# SWITCHING.net
KiCad netlist of a schematic drawn in Altium Designer
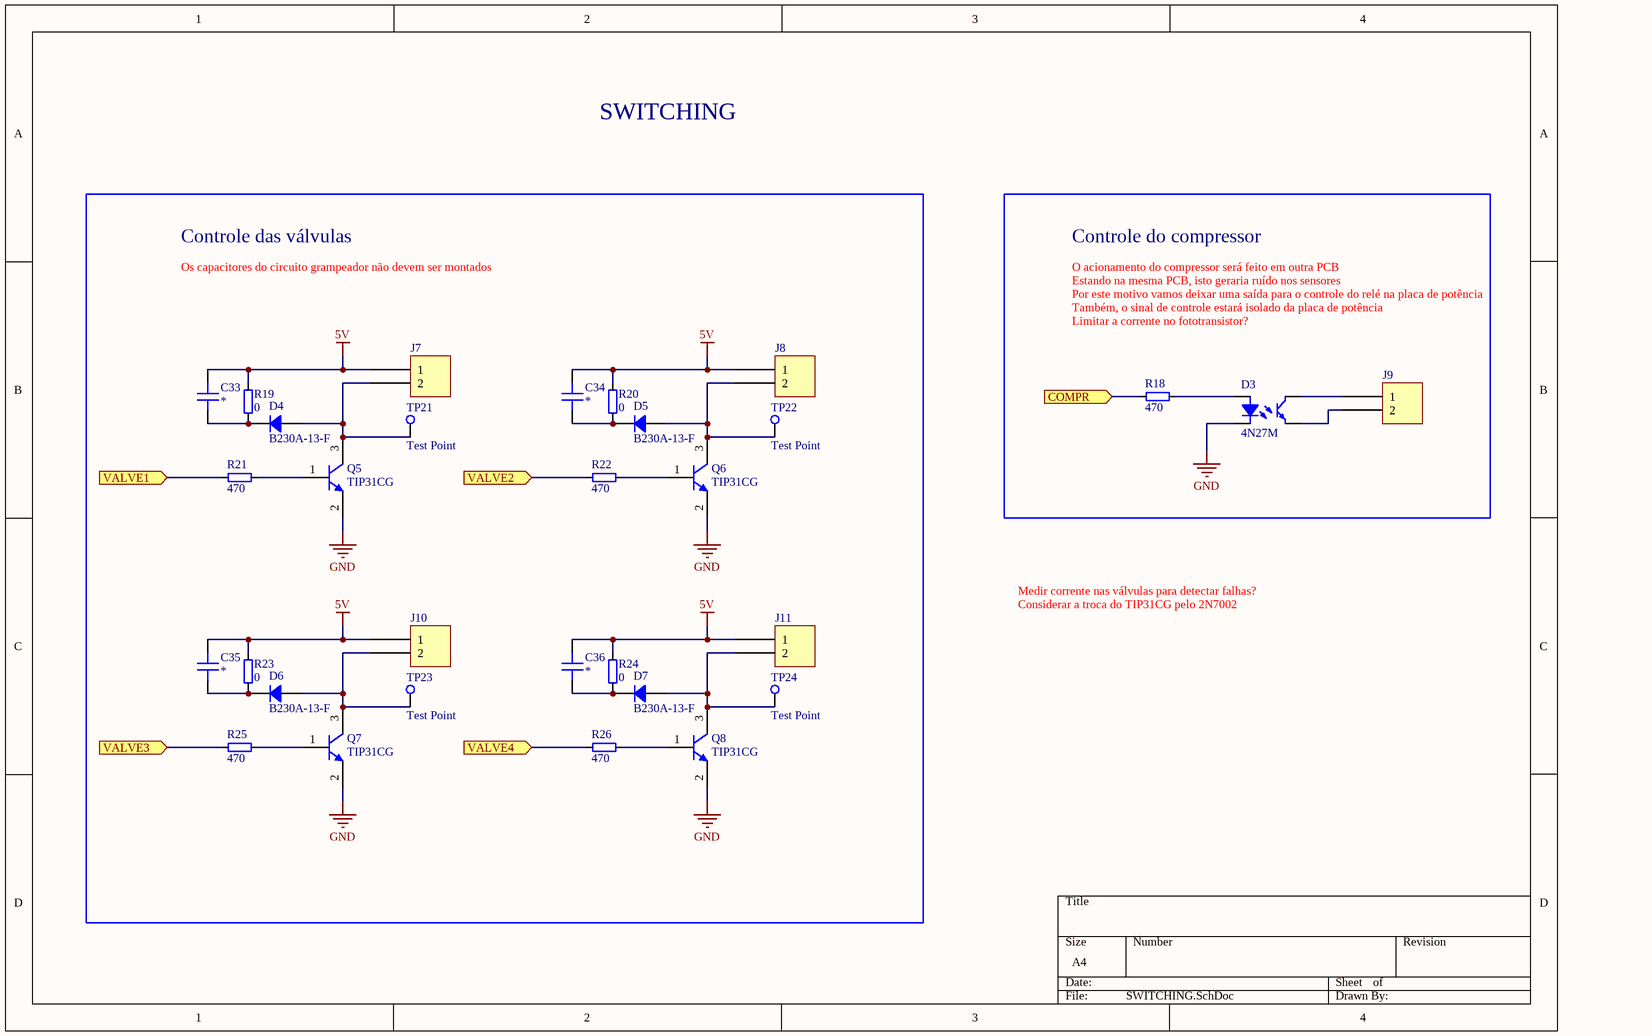
[diagram p0: SWITCHING.SchDoc]

(export (version "E")
  (design (tool "Eeschema 10.0.6"))
  (components
    (comp (ref "C33")
      (value "*")
      (footprint "C_0805")
      (description "Generic SMD 0805 Capacitor")
      (libsource (lib "RespiradorLib") (part "C_0805"))
    )
    (comp (ref "C34")
      (value "*")
      (footprint "C_0805")
      (description "Generic SMD 0805 Capacitor")
      (libsource (lib "RespiradorLib") (part "C_0805"))
    )
    (comp (ref "C35")
      (value "*")
      (footprint "C_0805")
      (description "Generic SMD 0805 Capacitor")
      (libsource (lib "RespiradorLib") (part "C_0805"))
    )
    (comp (ref "C36")
      (value "*")
      (footprint "C_0805")
      (description "Generic SMD 0805 Capacitor")
      (libsource (lib "RespiradorLib") (part "C_0805"))
    )
    (comp (ref "D3")
      (value "4N27M")
      (footprint "DIP6")
      (description "4N27M OPTOCOUPLER TRANS-OUT 6-DIP")
      (libsource (lib "RespiradorLib") (part "Optocoupler 4N27M"))
    )
    (comp (ref "D4")
      (value "B230A-13-F")
      (footprint "DO-214AC")
      (description "DIODE SCHOTTKY 30V 2A SMA")
      (fields (field (name "VOLTAGE") "30V"))
      (libsource (lib "RespiradorLib") (part "DIODE_B230A-13-F"))
    )
    (comp (ref "D5")
      (value "B230A-13-F")
      (footprint "DO-214AC")
      (description "DIODE SCHOTTKY 30V 2A SMA")
      (fields (field (name "VOLTAGE") "30V"))
      (libsource (lib "RespiradorLib") (part "DIODE_B230A-13-F"))
    )
    (comp (ref "D6")
      (value "B230A-13-F")
      (footprint "DO-214AC")
      (description "DIODE SCHOTTKY 30V 2A SMA")
      (fields (field (name "VOLTAGE") "30V"))
      (libsource (lib "RespiradorLib") (part "DIODE_B230A-13-F"))
    )
    (comp (ref "D7")
      (value "B230A-13-F")
      (footprint "DO-214AC")
      (description "DIODE SCHOTTKY 30V 2A SMA")
      (fields (field (name "VOLTAGE") "30V"))
      (libsource (lib "RespiradorLib") (part "DIODE_B230A-13-F"))
    )
    (comp (ref "J7")
      (value "Term Block 2 Pin 2.54mm")
      (footprint "TERM_BLOCK2PIN")
      (description "CONN TERM BLOCK 2.54MM 2POS 125V 6A")
      (libsource (lib "RespiradorLib") (part "TERM BLOCK 2 PIN_1"))
    )
    (comp (ref "J8")
      (value "Term Block 2 Pin 2.54mm")
      (footprint "TERM_BLOCK2PIN")
      (description "CONN TERM BLOCK 2.54MM 2POS 125V 6A")
      (libsource (lib "RespiradorLib") (part "TERM BLOCK 2 PIN_1"))
    )
    (comp (ref "J9")
      (value "Term Block 2 Pin 2.54mm")
      (footprint "TERM_BLOCK2PIN")
      (description "CONN TERM BLOCK 2.54MM 2POS 125V 6A")
      (libsource (lib "RespiradorLib") (part "TERM BLOCK 2 PIN_1"))
    )
    (comp (ref "J10")
      (value "Term Block 2 Pin 2.54mm")
      (footprint "TERM_BLOCK2PIN")
      (description "CONN TERM BLOCK 2.54MM 2POS 125V 6A")
      (libsource (lib "RespiradorLib") (part "TERM BLOCK 2 PIN_1"))
    )
    (comp (ref "J11")
      (value "Term Block 2 Pin 2.54mm")
      (footprint "TERM_BLOCK2PIN")
      (description "CONN TERM BLOCK 2.54MM 2POS 125V 6A")
      (libsource (lib "RespiradorLib") (part "TERM BLOCK 2 PIN_1"))
    )
    (comp (ref "Q5")
      (value "TIP31CG")
      (footprint "TO-220")
      (description "BJT 3A 100V 40W NPN")
      (libsource (lib "RespiradorLib") (part "TRANS_TIP31CG"))
    )
    (comp (ref "Q6")
      (value "TIP31CG")
      (footprint "TO-220")
      (description "BJT 3A 100V 40W NPN")
      (libsource (lib "RespiradorLib") (part "TRANS_TIP31CG"))
    )
    (comp (ref "Q7")
      (value "TIP31CG")
      (footprint "TO-220")
      (description "BJT 3A 100V 40W NPN")
      (libsource (lib "RespiradorLib") (part "TRANS_TIP31CG"))
    )
    (comp (ref "Q8")
      (value "TIP31CG")
      (footprint "TO-220")
      (description "BJT 3A 100V 40W NPN")
      (libsource (lib "RespiradorLib") (part "TRANS_TIP31CG"))
    )
    (comp (ref "R18")
      (value "470")
      (footprint "R_0805")
      (description "RES 470 OHM 1/8W 1% 0805 SMD")
      (fields (field (name "MANUFACTURER") "Panasonic - ECG") (field (name "VOLTAGE") "150V"))
      (libsource (lib "RespiradorLib") (part "R_0805_ERJ-6ENF4700V"))
    )
    (comp (ref "R19")
      (value "0")
      (footprint "R_0805")
      (description "RES 0 OHM 1/8W 1% 0805 SMD")
      (fields (field (name "MANUFACTURER") "Panasonic - ECG") (field (name "PART NUMBER") "ERJ-6GEY0R00V"))
      (libsource (lib "RespiradorLib") (part "R_0805_ERJ-6GEY0R00V"))
    )
    (comp (ref "R20")
      (value "0")
      (footprint "R_0805")
      (description "RES 0 OHM 1/8W 1% 0805 SMD")
      (fields (field (name "MANUFACTURER") "Panasonic - ECG") (field (name "PART NUMBER") "ERJ-6GEY0R00V"))
      (libsource (lib "RespiradorLib") (part "R_0805_ERJ-6GEY0R00V"))
    )
    (comp (ref "R21")
      (value "470")
      (footprint "R_0805")
      (description "RES 470 OHM 1/8W 1% 0805 SMD")
      (fields (field (name "MANUFACTURER") "Panasonic - ECG") (field (name "VOLTAGE") "150V"))
      (libsource (lib "RespiradorLib") (part "R_0805_ERJ-6ENF4700V"))
    )
    (comp (ref "R22")
      (value "470")
      (footprint "R_0805")
      (description "RES 470 OHM 1/8W 1% 0805 SMD")
      (fields (field (name "MANUFACTURER") "Panasonic - ECG") (field (name "VOLTAGE") "150V"))
      (libsource (lib "RespiradorLib") (part "R_0805_ERJ-6ENF4700V"))
    )
    (comp (ref "R23")
      (value "0")
      (footprint "R_0805")
      (description "RES 0 OHM 1/8W 1% 0805 SMD")
      (fields (field (name "MANUFACTURER") "Panasonic - ECG") (field (name "PART NUMBER") "ERJ-6GEY0R00V"))
      (libsource (lib "RespiradorLib") (part "R_0805_ERJ-6GEY0R00V"))
    )
    (comp (ref "R24")
      (value "0")
      (footprint "R_0805")
      (description "RES 0 OHM 1/8W 1% 0805 SMD")
      (fields (field (name "MANUFACTURER") "Panasonic - ECG") (field (name "PART NUMBER") "ERJ-6GEY0R00V"))
      (libsource (lib "RespiradorLib") (part "R_0805_ERJ-6GEY0R00V"))
    )
    (comp (ref "R25")
      (value "470")
      (footprint "R_0805")
      (description "RES 470 OHM 1/8W 1% 0805 SMD")
      (fields (field (name "MANUFACTURER") "Panasonic - ECG") (field (name "VOLTAGE") "150V"))
      (libsource (lib "RespiradorLib") (part "R_0805_ERJ-6ENF4700V"))
    )
    (comp (ref "R26")
      (value "470")
      (footprint "R_0805")
      (description "RES 470 OHM 1/8W 1% 0805 SMD")
      (fields (field (name "MANUFACTURER") "Panasonic - ECG") (field (name "VOLTAGE") "150V"))
      (libsource (lib "RespiradorLib") (part "R_0805_ERJ-6ENF4700V"))
    )
    (comp (ref "TP21")
      (value "Test Point")
      (footprint "Test_Point")
      (libsource (lib "RespiradorLib") (part "Test Point"))
    )
    (comp (ref "TP22")
      (value "Test Point")
      (footprint "Test_Point")
      (libsource (lib "RespiradorLib") (part "Test Point"))
    )
    (comp (ref "TP23")
      (value "Test Point")
      (footprint "Test_Point")
      (libsource (lib "RespiradorLib") (part "Test Point"))
    )
    (comp (ref "TP24")
      (value "Test Point")
      (footprint "Test_Point")
      (libsource (lib "RespiradorLib") (part "Test Point"))
    )
  )
  (nets
    (net (code "1") (name "/COMPR") (class "Default")
      (node (ref "R18") (pin "1") (pinfunction "1_1") (pintype "passive"))
    )
    (net (code "2") (name "/VALVE1") (class "Default")
      (node (ref "R21") (pin "1") (pinfunction "1_1") (pintype "passive"))
    )
    (net (code "3") (name "/VALVE2") (class "Default")
      (node (ref "R22") (pin "1") (pinfunction "1_1") (pintype "passive"))
    )
    (net (code "4") (name "/VALVE3") (class "Default")
      (node (ref "R25") (pin "1") (pinfunction "1_1") (pintype "passive"))
    )
    (net (code "5") (name "/VALVE4") (class "Default")
      (node (ref "R26") (pin "1") (pinfunction "1_1") (pintype "passive"))
    )
    (net (code "6") (name "5V") (class "Default")
      (node (ref "C33") (pin "2") (pinfunction "2_2") (pintype "passive"))
      (node (ref "C34") (pin "2") (pinfunction "2_2") (pintype "passive"))
      (node (ref "C35") (pin "2") (pinfunction "2_2") (pintype "passive"))
      (node (ref "C36") (pin "2") (pinfunction "2_2") (pintype "passive"))
      (node (ref "J10") (pin "1") (pinfunction "1_1") (pintype "passive"))
      (node (ref "J11") (pin "1") (pinfunction "1_1") (pintype "passive"))
      (node (ref "J7") (pin "1") (pinfunction "1_1") (pintype "passive"))
      (node (ref "J8") (pin "1") (pinfunction "1_1") (pintype "passive"))
      (node (ref "R19") (pin "2") (pinfunction "2_2") (pintype "passive"))
      (node (ref "R20") (pin "2") (pinfunction "2_2") (pintype "passive"))
      (node (ref "R23") (pin "2") (pinfunction "2_2") (pintype "passive"))
      (node (ref "R24") (pin "2") (pinfunction "2_2") (pintype "passive"))
    )
    (net (code "7") (name "GND") (class "Default")
      (node (ref "D3") (pin "2") (pinfunction "2_2") (pintype "passive"))
      (node (ref "Q5") (pin "2") (pinfunction "E_2") (pintype "passive"))
      (node (ref "Q6") (pin "2") (pinfunction "E_2") (pintype "passive"))
      (node (ref "Q7") (pin "2") (pinfunction "E_2") (pintype "passive"))
      (node (ref "Q8") (pin "2") (pinfunction "E_2") (pintype "passive"))
    )
    (net (code "8") (name "Net-(C33-Pad1)") (class "Default")
      (node (ref "C33") (pin "1") (pinfunction "1_1") (pintype "passive"))
      (node (ref "D4") (pin "2") (pinfunction "2_2") (pintype "passive"))
      (node (ref "R19") (pin "1") (pinfunction "1_1") (pintype "passive"))
    )
    (net (code "9") (name "Net-(C34-Pad1)") (class "Default")
      (node (ref "C34") (pin "1") (pinfunction "1_1") (pintype "passive"))
      (node (ref "D5") (pin "2") (pinfunction "2_2") (pintype "passive"))
      (node (ref "R20") (pin "1") (pinfunction "1_1") (pintype "passive"))
    )
    (net (code "10") (name "Net-(C35-Pad1)") (class "Default")
      (node (ref "C35") (pin "1") (pinfunction "1_1") (pintype "passive"))
      (node (ref "D6") (pin "2") (pinfunction "2_2") (pintype "passive"))
      (node (ref "R23") (pin "1") (pinfunction "1_1") (pintype "passive"))
    )
    (net (code "11") (name "Net-(C36-Pad1)") (class "Default")
      (node (ref "C36") (pin "1") (pinfunction "1_1") (pintype "passive"))
      (node (ref "D7") (pin "2") (pinfunction "2_2") (pintype "passive"))
      (node (ref "R24") (pin "1") (pinfunction "1_1") (pintype "passive"))
    )
    (net (code "12") (name "Net-(D3-Pad1)") (class "Default")
      (node (ref "D3") (pin "1") (pinfunction "1_1") (pintype "passive"))
      (node (ref "R18") (pin "2") (pinfunction "2_2") (pintype "passive"))
    )
    (net (code "13") (name "Net-(D3-Pad3)") (class "Default")
      (node (ref "D3") (pin "3") (pinfunction "3_3") (pintype "passive"))
      (node (ref "J9") (pin "2") (pinfunction "2_2") (pintype "passive"))
    )
    (net (code "14") (name "Net-(D3-Pad4)") (class "Default")
      (node (ref "D3") (pin "4") (pinfunction "4_4") (pintype "passive"))
      (node (ref "J9") (pin "1") (pinfunction "1_1") (pintype "passive"))
    )
    (net (code "15") (name "Net-(Q5-B)") (class "Default")
      (node (ref "Q5") (pin "1") (pinfunction "B_1") (pintype "passive"))
      (node (ref "R21") (pin "2") (pinfunction "2_2") (pintype "passive"))
    )
    (net (code "16") (name "Net-(Q5-C)") (class "Default")
      (node (ref "D4") (pin "1") (pinfunction "1_1") (pintype "passive"))
      (node (ref "J7") (pin "2") (pinfunction "2_2") (pintype "passive"))
      (node (ref "Q5") (pin "3") (pinfunction "C_3") (pintype "passive"))
      (node (ref "TP21") (pin "1") (pinfunction "TP_1") (pintype "passive"))
    )
    (net (code "17") (name "Net-(Q6-B)") (class "Default")
      (node (ref "Q6") (pin "1") (pinfunction "B_1") (pintype "passive"))
      (node (ref "R22") (pin "2") (pinfunction "2_2") (pintype "passive"))
    )
    (net (code "18") (name "Net-(Q6-C)") (class "Default")
      (node (ref "D5") (pin "1") (pinfunction "1_1") (pintype "passive"))
      (node (ref "J8") (pin "2") (pinfunction "2_2") (pintype "passive"))
      (node (ref "Q6") (pin "3") (pinfunction "C_3") (pintype "passive"))
      (node (ref "TP22") (pin "1") (pinfunction "TP_1") (pintype "passive"))
    )
    (net (code "19") (name "Net-(Q7-B)") (class "Default")
      (node (ref "Q7") (pin "1") (pinfunction "B_1") (pintype "passive"))
      (node (ref "R25") (pin "2") (pinfunction "2_2") (pintype "passive"))
    )
    (net (code "20") (name "Net-(Q7-C)") (class "Default")
      (node (ref "D6") (pin "1") (pinfunction "1_1") (pintype "passive"))
      (node (ref "J10") (pin "2") (pinfunction "2_2") (pintype "passive"))
      (node (ref "Q7") (pin "3") (pinfunction "C_3") (pintype "passive"))
      (node (ref "TP23") (pin "1") (pinfunction "TP_1") (pintype "passive"))
    )
    (net (code "21") (name "Net-(Q8-B)") (class "Default")
      (node (ref "Q8") (pin "1") (pinfunction "B_1") (pintype "passive"))
      (node (ref "R26") (pin "2") (pinfunction "2_2") (pintype "passive"))
    )
    (net (code "22") (name "Net-(Q8-C)") (class "Default")
      (node (ref "D7") (pin "1") (pinfunction "1_1") (pintype "passive"))
      (node (ref "J11") (pin "2") (pinfunction "2_2") (pintype "passive"))
      (node (ref "Q8") (pin "3") (pinfunction "C_3") (pintype "passive"))
      (node (ref "TP24") (pin "1") (pinfunction "TP_1") (pintype "passive"))
    )
  )
)
